# tyraka2_1.net
KiCad netlist of a schematic drawn in EAGLE
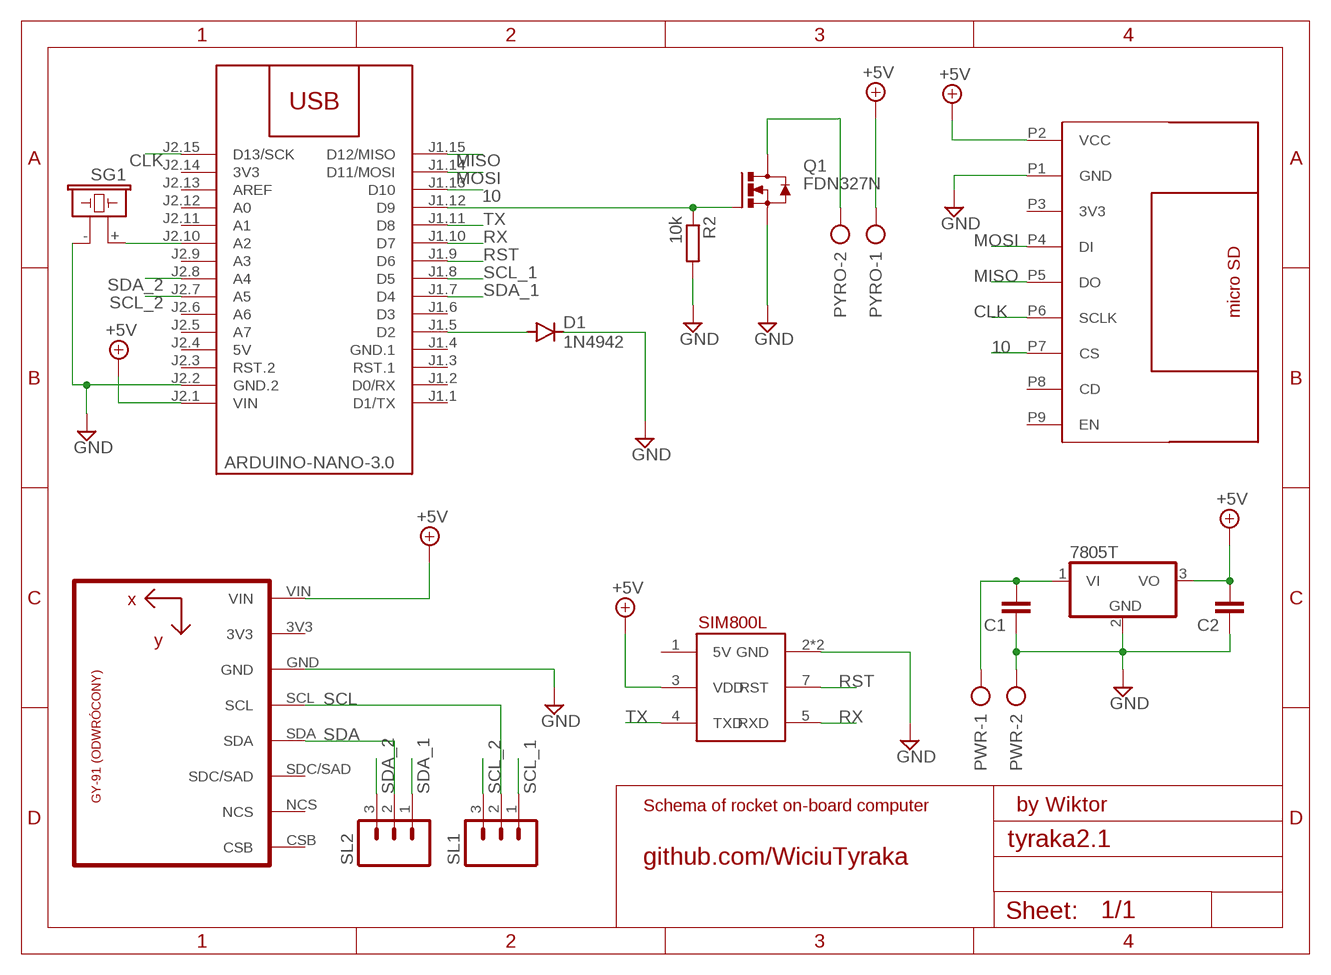
[diagram p0: schematic, sheet 1]

(export (version "E")
  (design (tool "Eeschema 10.0.6"))
  (components
    (comp (ref "C1")
      (value "C2.5/4")
      (footprint "eagle-import:C2.5-4")
      (libsource (lib "eagle-import") (part "C2.5/4"))
    )
    (comp (ref "C2")
      (value "C2.5/4")
      (footprint "eagle-import:C2.5-4")
      (libsource (lib "eagle-import") (part "C2.5/4"))
    )
    (comp (ref "D1")
      (value "1N4942")
      (footprint "eagle-import:DO41-10")
      (libsource (lib "eagle-import") (part "1N4942"))
    )
    (comp (ref "IC2")
      (value "7805T")
      (footprint "eagle-import:TO220H")
      (libsource (lib "eagle-import") (part "78T05"))
    )
    (comp (ref "M1")
      (value "ARDUINO-NANO-3.0")
      (footprint "eagle-import:ARDUINO-NANO-3.0")
      (libsource (lib "eagle-import") (part "ARDUINO-NANO-3.0"))
    )
    (comp (ref "PWR")
      (value "AK500/2")
      (footprint "eagle-import:AK500_2")
      (libsource (lib "eagle-import") (part "AK500/2"))
    )
    (comp (ref "PYRO")
      (value "AK500/2")
      (footprint "eagle-import:AK500_2")
      (libsource (lib "eagle-import") (part "AK500/2"))
    )
    (comp (ref "Q1")
      (value "FDN327N")
      (footprint "eagle-import:SOT23")
      (libsource (lib "eagle-import") (part "MOSFET_N_SOT231"))
    )
    (comp (ref "R2")
      (value "10k")
      (footprint "eagle-import:0204_5")
      (libsource (lib "eagle-import") (part "R-EU_0204/5"))
    )
    (comp (ref "SD1")
      (value "MICRO_SD")
      (footprint "eagle-import:MICRO_SD")
      (libsource (lib "eagle-import") (part "MICRO_SD"))
    )
    (comp (ref "SG1")
      (value "F/CM12P")
      (footprint "eagle-import:F_CM12P")
      (libsource (lib "eagle-import") (part "F/CM12P"))
    )
    (comp (ref "SL1")
      (value "M03")
      (footprint "eagle-import:03P")
      (libsource (lib "eagle-import") (part "M03"))
    )
    (comp (ref "SL2")
      (value "M03")
      (footprint "eagle-import:03P")
      (libsource (lib "eagle-import") (part "M03"))
    )
    (comp (ref "U$1")
      (value "SIM800L")
      (footprint "eagle-import:SIP")
      (libsource (lib "eagle-import") (part "SIM800L"))
    )
    (comp (ref "U1")
      (value "GY-521MPU6050")
      (footprint "eagle-import:GY-521")
      (libsource (lib "eagle-import") (part "GY-521MPU6050"))
    )
  )
  (nets
    (net (code "1") (name "+5V") (class "Default")
      (node (ref "C2") (pin "2") (pinfunction "2_2") (pintype "passive"))
      (node (ref "IC2") (pin "3") (pinfunction "VO_3") (pintype "passive"))
      (node (ref "M1") (pin "J2.1") (pinfunction "VIN_J2.1") (pintype "power_in"))
      (node (ref "PYRO") (pin "1") (pinfunction "KL_1") (pintype "passive"))
      (node (ref "SD1") (pin "P2") (pinfunction "VCC_P2") (pintype "power_in"))
      (node (ref "U$1") (pin "3") (pinfunction "VDD_3") (pintype "bidirectional"))
      (node (ref "U1") (pin "VIN") (pinfunction "VIN_VIN") (pintype "bidirectional"))
    )
    (net (code "2") (name "/3V3") (class "Default")
      (node (ref "M1") (pin "J2.14") (pinfunction "3V3_J2.14") (pintype "power_in"))
    )
    (net (code "3") (name "/5V") (class "Default")
      (node (ref "M1") (pin "J2.4") (pinfunction "5V_J2.4") (pintype "power_in"))
    )
    (net (code "4") (name "/10") (class "Default")
      (node (ref "M1") (pin "J1.13") (pinfunction "D10_J1.13") (pintype "bidirectional"))
      (node (ref "SD1") (pin "P7") (pinfunction "CS_P7") (pintype "bidirectional"))
    )
    (net (code "5") (name "/CLK") (class "Default")
      (node (ref "M1") (pin "J2.15") (pinfunction "D13/SCK_J2.15") (pintype "bidirectional"))
      (node (ref "SD1") (pin "P6") (pinfunction "SCLK_P6") (pintype "bidirectional"))
    )
    (net (code "6") (name "/GND.1") (class "Default")
      (node (ref "M1") (pin "J1.4") (pinfunction "GND.1_J1.4") (pintype "power_in"))
    )
    (net (code "7") (name "/MISO") (class "Default")
      (node (ref "M1") (pin "J1.15") (pinfunction "D12/MISO_J1.15") (pintype "bidirectional"))
      (node (ref "SD1") (pin "P5") (pinfunction "DO_P5") (pintype "bidirectional"))
    )
    (net (code "8") (name "/MOSI") (class "Default")
      (node (ref "M1") (pin "J1.14") (pinfunction "D11/MOSI_J1.14") (pintype "bidirectional"))
      (node (ref "SD1") (pin "P4") (pinfunction "DI_P4") (pintype "bidirectional"))
    )
    (net (code "9") (name "/RST") (class "Default")
      (node (ref "M1") (pin "J1.9") (pinfunction "D6_J1.9") (pintype "bidirectional"))
      (node (ref "U$1") (pin "7") (pinfunction "RST_7") (pintype "bidirectional"))
    )
    (net (code "10") (name "/RX") (class "Default")
      (node (ref "M1") (pin "J1.10") (pinfunction "D7_J1.10") (pintype "bidirectional"))
      (node (ref "U$1") (pin "5") (pinfunction "RXD_5") (pintype "bidirectional"))
    )
    (net (code "11") (name "/SCL") (class "Default")
      (node (ref "SL1") (pin "2") (pinfunction "2_2") (pintype "passive"))
      (node (ref "U1") (pin "SCL") (pinfunction "SCL_SCL") (pintype "bidirectional"))
    )
    (net (code "12") (name "/SCL_1") (class "Default")
      (node (ref "M1") (pin "J1.8") (pinfunction "D5_J1.8") (pintype "bidirectional"))
      (node (ref "SL1") (pin "1") (pinfunction "1_1") (pintype "passive"))
    )
    (net (code "13") (name "/SCL_2") (class "Default")
      (node (ref "M1") (pin "J2.7") (pinfunction "A5_J2.7") (pintype "bidirectional"))
      (node (ref "SL1") (pin "3") (pinfunction "3_3") (pintype "passive"))
    )
    (net (code "14") (name "/SDA") (class "Default")
      (node (ref "SL2") (pin "2") (pinfunction "2_2") (pintype "passive"))
      (node (ref "U1") (pin "SDA") (pinfunction "SDA_SDA") (pintype "bidirectional"))
    )
    (net (code "15") (name "/SDA_1") (class "Default")
      (node (ref "M1") (pin "J1.7") (pinfunction "D4_J1.7") (pintype "bidirectional"))
      (node (ref "SL2") (pin "1") (pinfunction "1_1") (pintype "passive"))
    )
    (net (code "16") (name "/SDA_2") (class "Default")
      (node (ref "M1") (pin "J2.8") (pinfunction "A4_J2.8") (pintype "bidirectional"))
      (node (ref "SL2") (pin "3") (pinfunction "3_3") (pintype "passive"))
    )
    (net (code "17") (name "/TX") (class "Default")
      (node (ref "M1") (pin "J1.11") (pinfunction "D8_J1.11") (pintype "bidirectional"))
      (node (ref "U$1") (pin "4") (pinfunction "TXD_4") (pintype "bidirectional"))
    )
    (net (code "18") (name "GND") (class "Default")
      (node (ref "C1") (pin "1") (pinfunction "1_1") (pintype "passive"))
      (node (ref "C2") (pin "1") (pinfunction "1_1") (pintype "passive"))
      (node (ref "D1") (pin "C") (pinfunction "C_C") (pintype "passive"))
      (node (ref "IC2") (pin "2") (pinfunction "GND_2") (pintype "passive"))
      (node (ref "M1") (pin "J2.2") (pinfunction "GND.2_J2.2") (pintype "power_in"))
      (node (ref "PWR") (pin "2") (pinfunction "KL_2") (pintype "passive"))
      (node (ref "Q1") (pin "2") (pinfunction "S_2") (pintype "passive"))
      (node (ref "R2") (pin "2") (pinfunction "2_2") (pintype "passive"))
      (node (ref "SD1") (pin "P1") (pinfunction "GND_P1") (pintype "power_in"))
      (node (ref "SG1") (pin "-") (pinfunction "2_-") (pintype "passive"))
      (node (ref "U$1") (pin "2") (pinfunction "GND_2") (pintype "bidirectional"))
      (node (ref "U$1") (pin "6") (pinfunction "GND_6") (pintype "bidirectional"))
      (node (ref "U1") (pin "GND") (pinfunction "GND_GND") (pintype "bidirectional"))
    )
    (net (code "19") (name "Net-(IC2-VI)") (class "Default")
      (node (ref "C1") (pin "2") (pinfunction "2_2") (pintype "passive"))
      (node (ref "IC2") (pin "1") (pinfunction "VI_1") (pintype "input"))
      (node (ref "PWR") (pin "1") (pinfunction "KL_1") (pintype "passive"))
    )
    (net (code "20") (name "Net-(M1-A2)") (class "Default")
      (node (ref "M1") (pin "J2.10") (pinfunction "A2_J2.10") (pintype "bidirectional"))
      (node (ref "SG1") (pin "+") (pinfunction "1_+") (pintype "passive"))
    )
    (net (code "21") (name "Net-(M1-D2)") (class "Default")
      (node (ref "D1") (pin "A") (pinfunction "A_A") (pintype "passive"))
      (node (ref "M1") (pin "J1.5") (pinfunction "D2_J1.5") (pintype "bidirectional"))
    )
    (net (code "22") (name "Net-(M1-D9)") (class "Default")
      (node (ref "M1") (pin "J1.12") (pinfunction "D9_J1.12") (pintype "bidirectional"))
      (node (ref "Q1") (pin "1") (pinfunction "G_1") (pintype "passive"))
      (node (ref "R2") (pin "1") (pinfunction "1_1") (pintype "passive"))
    )
    (net (code "23") (name "Net-(PYROB-KL)") (class "Default")
      (node (ref "PYRO") (pin "2") (pinfunction "KL_2") (pintype "passive"))
      (node (ref "Q1") (pin "3") (pinfunction "D_3") (pintype "passive"))
    )
    (net (code "24") (name "unconnected-(M1-A0-PadJ2.12)") (class "Default")
      (node (ref "M1") (pin "J2.12") (pinfunction "A0_J2.12") (pintype "bidirectional"))
    )
    (net (code "25") (name "unconnected-(M1-A1-PadJ2.11)") (class "Default")
      (node (ref "M1") (pin "J2.11") (pinfunction "A1_J2.11") (pintype "bidirectional"))
    )
    (net (code "26") (name "unconnected-(M1-A3-PadJ2.9)") (class "Default")
      (node (ref "M1") (pin "J2.9") (pinfunction "A3_J2.9") (pintype "bidirectional"))
    )
    (net (code "27") (name "unconnected-(M1-A6-PadJ2.6)") (class "Default")
      (node (ref "M1") (pin "J2.6") (pinfunction "A6_J2.6") (pintype "bidirectional"))
    )
    (net (code "28") (name "unconnected-(M1-A7-PadJ2.5)") (class "Default")
      (node (ref "M1") (pin "J2.5") (pinfunction "A7_J2.5") (pintype "bidirectional"))
    )
    (net (code "29") (name "unconnected-(M1-AREF-PadJ2.13)") (class "Default")
      (node (ref "M1") (pin "J2.13") (pinfunction "AREF_J2.13") (pintype "bidirectional"))
    )
    (net (code "30") (name "unconnected-(M1-D0{slash}RX-PadJ1.2)") (class "Default")
      (node (ref "M1") (pin "J1.2") (pinfunction "D0/RX_J1.2") (pintype "bidirectional"))
    )
    (net (code "31") (name "unconnected-(M1-D1{slash}TX-PadJ1.1)") (class "Default")
      (node (ref "M1") (pin "J1.1") (pinfunction "D1/TX_J1.1") (pintype "bidirectional"))
    )
    (net (code "32") (name "unconnected-(M1-D3-PadJ1.6)") (class "Default")
      (node (ref "M1") (pin "J1.6") (pinfunction "D3_J1.6") (pintype "bidirectional"))
    )
    (net (code "33") (name "unconnected-(M1-RST.1-PadJ1.3)") (class "Default")
      (node (ref "M1") (pin "J1.3") (pinfunction "RST.1_J1.3") (pintype "bidirectional"))
    )
    (net (code "34") (name "unconnected-(M1-RST.2-PadJ2.3)") (class "Default")
      (node (ref "M1") (pin "J2.3") (pinfunction "RST.2_J2.3") (pintype "bidirectional"))
    )
    (net (code "35") (name "unconnected-(SD1-3V3-PadP3)") (class "Default")
      (node (ref "SD1") (pin "P3") (pinfunction "3V3_P3") (pintype "bidirectional"))
    )
    (net (code "36") (name "unconnected-(SD1-CD-PadP8)") (class "Default")
      (node (ref "SD1") (pin "P8") (pinfunction "CD_P8") (pintype "bidirectional"))
    )
    (net (code "37") (name "unconnected-(SD1-EN-PadP9)") (class "Default")
      (node (ref "SD1") (pin "P9") (pinfunction "EN_P9") (pintype "bidirectional"))
    )
    (net (code "38") (name "unconnected-(U$1-5V-Pad1)") (class "Default")
      (node (ref "U$1") (pin "1") (pinfunction "5V_1") (pintype "bidirectional"))
    )
    (net (code "39") (name "unconnected-(U1-Pad3V3)") (class "Default")
      (node (ref "U1") (pin "3V3") (pinfunction "3V3_3V3") (pintype "bidirectional"))
    )
    (net (code "40") (name "unconnected-(U1-PadCSB)") (class "Default")
      (node (ref "U1") (pin "CSB") (pinfunction "CSB_CSB") (pintype "bidirectional"))
    )
    (net (code "41") (name "unconnected-(U1-PadNCS)") (class "Default")
      (node (ref "U1") (pin "NCS") (pinfunction "NCS_NCS") (pintype "bidirectional"))
    )
    (net (code "42") (name "unconnected-(U1-PadSDC{slash}SAD)") (class "Default")
      (node (ref "U1") (pin "SDC/SAD") (pinfunction "SDC/SAD_SDC/SAD") (pintype "bidirectional"))
    )
  )
)
